# pcb.net
KiCad netlist of a schematic drawn in EAGLE
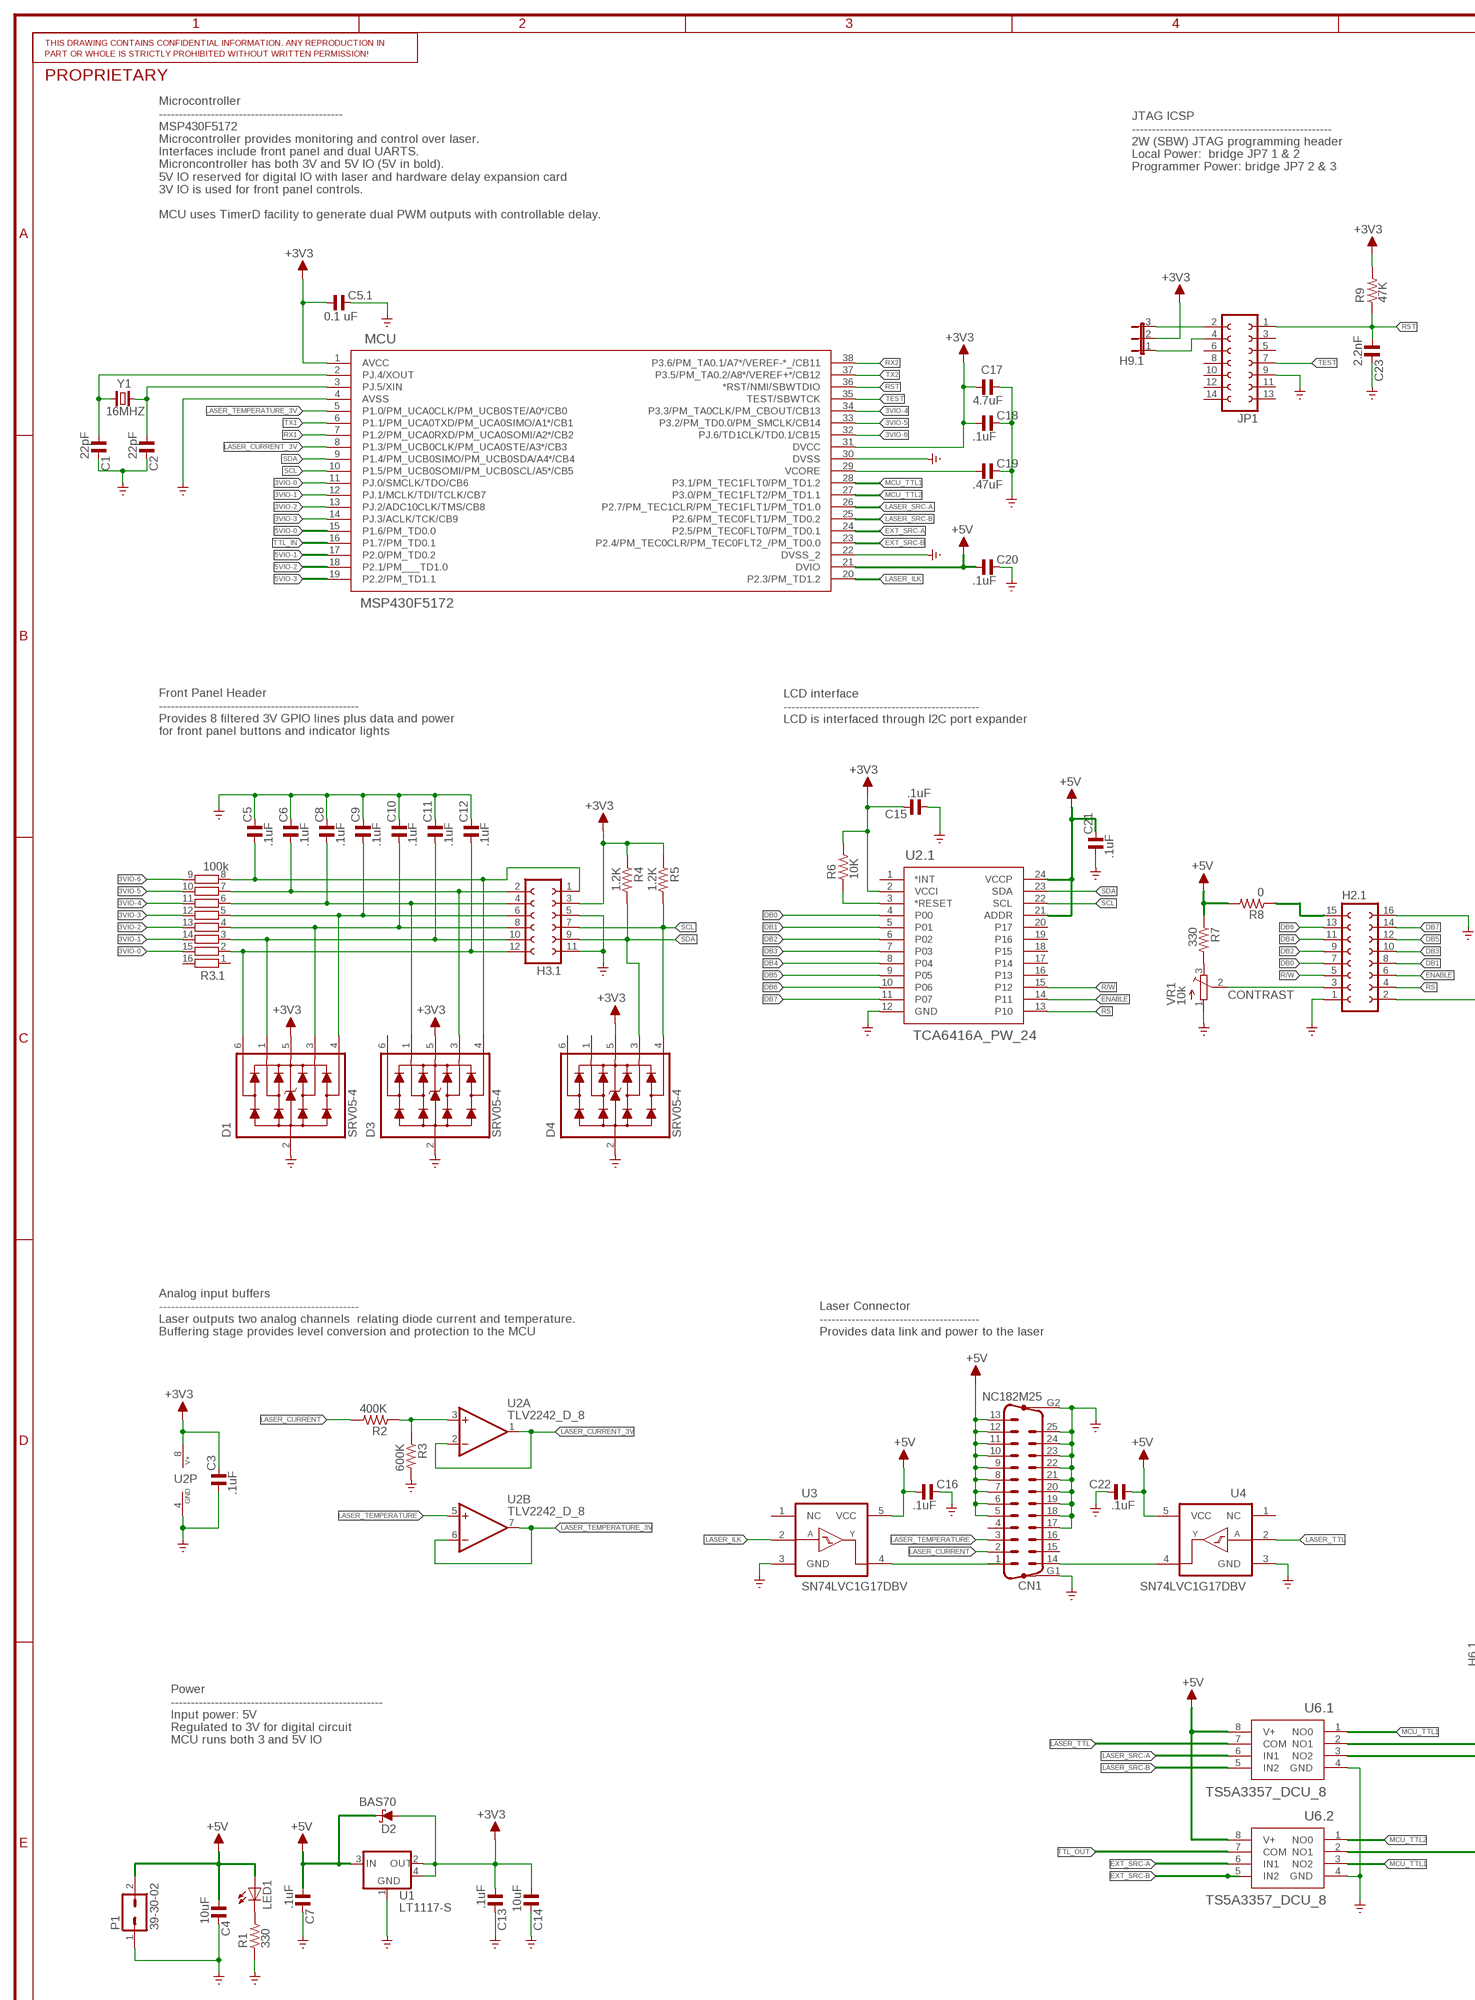
[diagram p0: schematic, sheet 1, part 1 of 3]
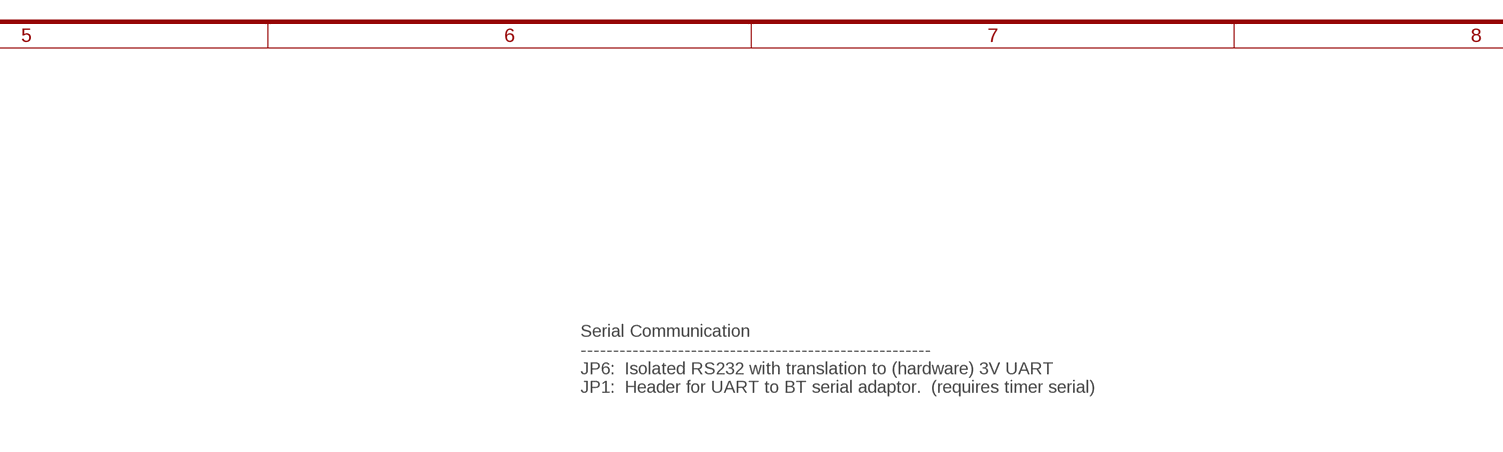
[diagram p1: schematic, sheet 1, part 2 of 3]
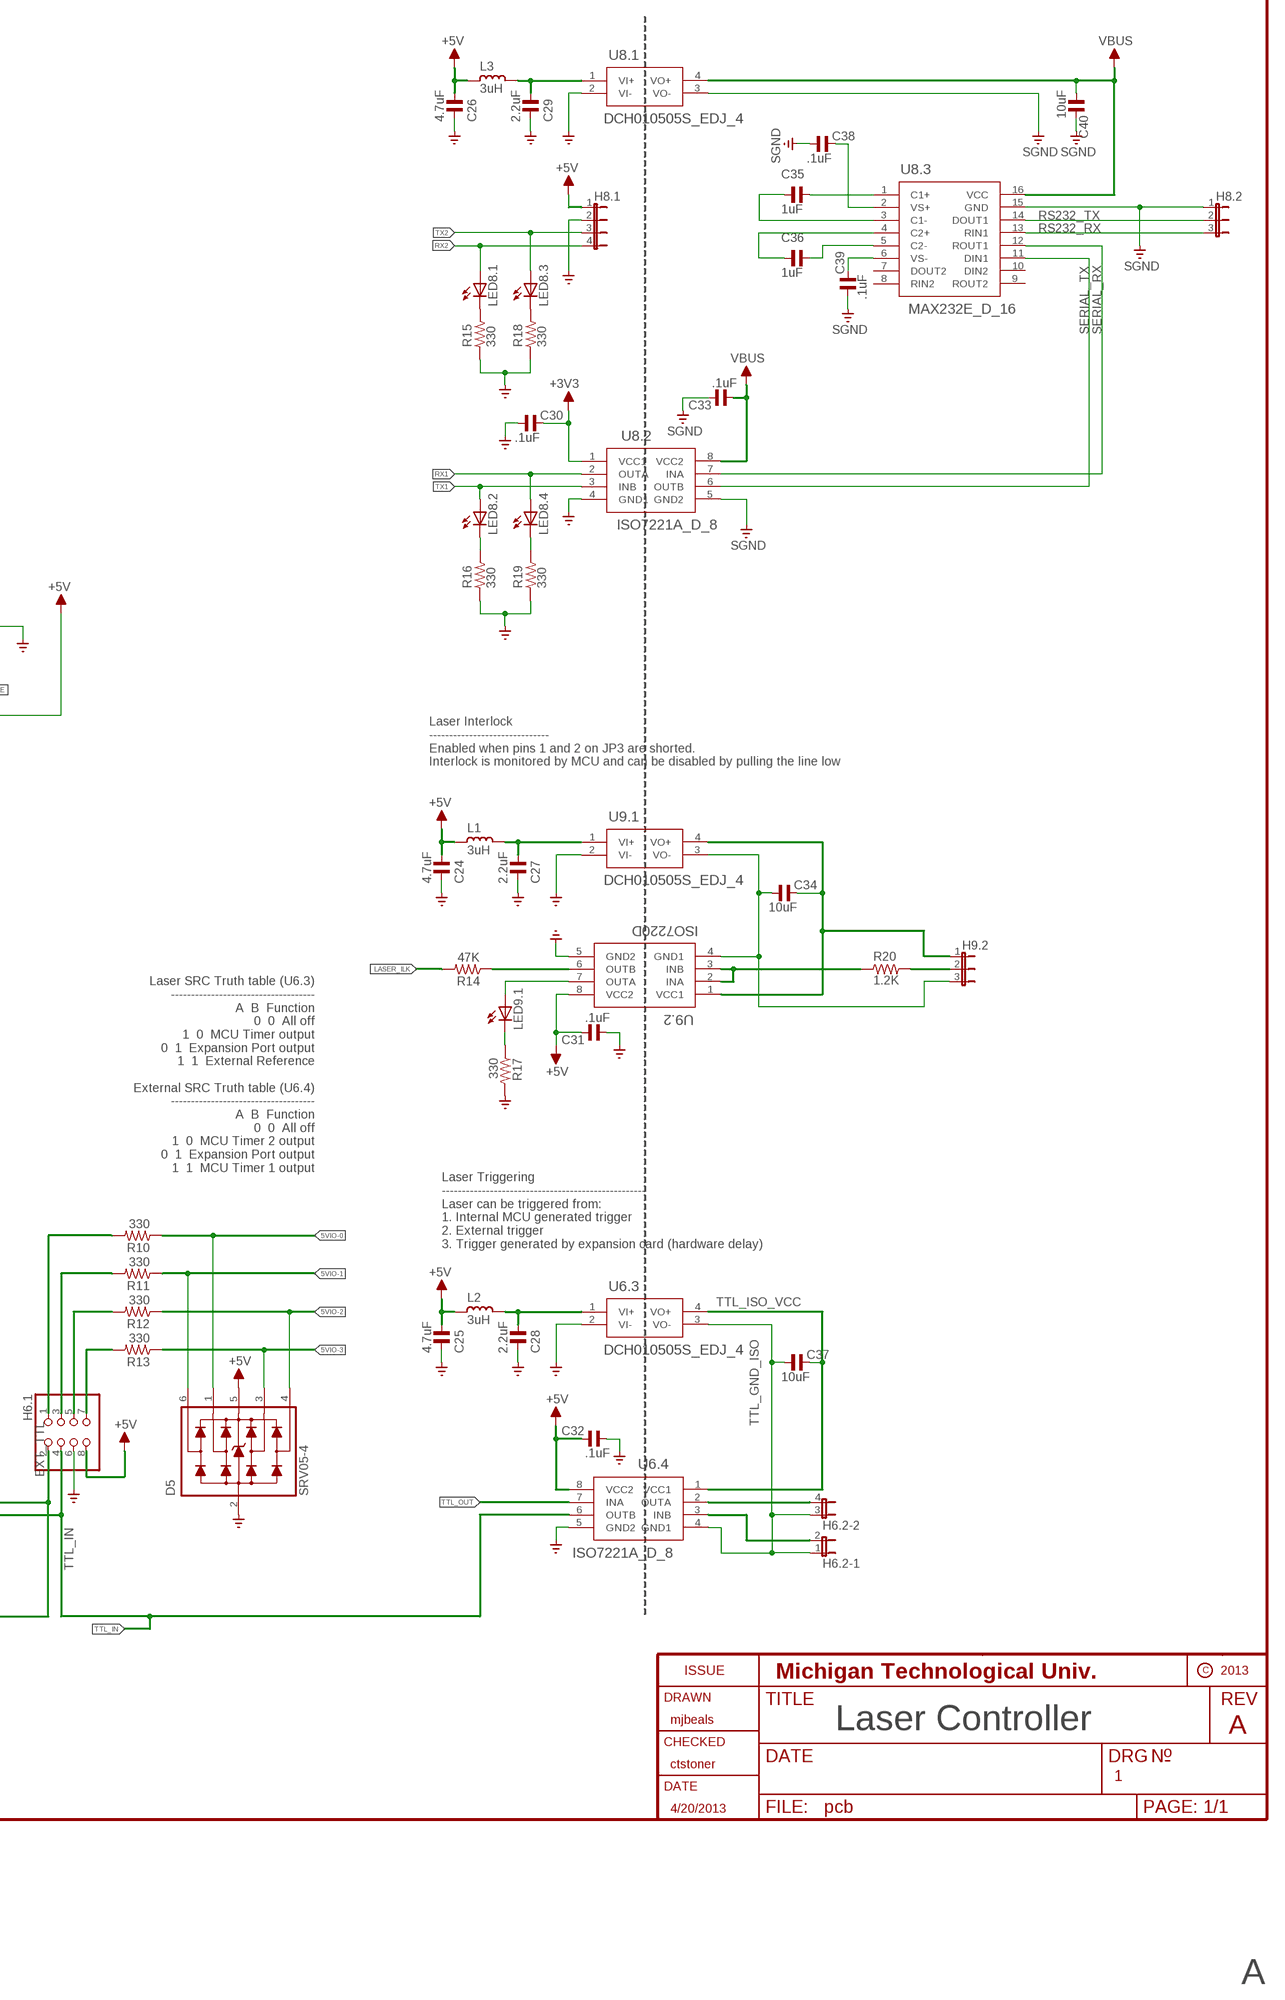
[diagram p2: schematic, sheet 1, part 3 of 3]

(export (version "E")
  (design (tool "Eeschema 10.0.6"))
  (components
    (comp (ref "C1")
      (value "22pF")
      (footprint "eagle-import:C0603")
      (libsource (lib "eagle-import") (part "C_0603"))
    )
    (comp (ref "C2")
      (value "22pF")
      (footprint "eagle-import:C0603")
      (libsource (lib "eagle-import") (part "C_0603"))
    )
    (comp (ref "C3")
      (value ".1uF")
      (footprint "eagle-import:C0603")
      (libsource (lib "eagle-import") (part "C_0603"))
    )
    (comp (ref "C4")
      (value "10uF")
      (footprint "eagle-import:C0603")
      (libsource (lib "eagle-import") (part "C_0603"))
    )
    (comp (ref "C5")
      (value ".1uF")
      (footprint "eagle-import:C0603")
      (libsource (lib "eagle-import") (part "C_0603"))
    )
    (comp (ref "C5.1")
      (value "0.1 uF")
      (footprint "eagle-import:C0603")
      (libsource (lib "eagle-import") (part "C_0603"))
    )
    (comp (ref "C6")
      (value ".1uF")
      (footprint "eagle-import:C0603")
      (libsource (lib "eagle-import") (part "C_0603"))
    )
    (comp (ref "C7")
      (value ".1uF")
      (footprint "eagle-import:C0603")
      (libsource (lib "eagle-import") (part "C_0603"))
    )
    (comp (ref "C8")
      (value ".1uF")
      (footprint "eagle-import:C0603")
      (libsource (lib "eagle-import") (part "C_0603"))
    )
    (comp (ref "C9")
      (value ".1uF")
      (footprint "eagle-import:C0603")
      (libsource (lib "eagle-import") (part "C_0603"))
    )
    (comp (ref "C10")
      (value ".1uF")
      (footprint "eagle-import:C0603")
      (libsource (lib "eagle-import") (part "C_0603"))
    )
    (comp (ref "C11")
      (value ".1uF")
      (footprint "eagle-import:C0603")
      (libsource (lib "eagle-import") (part "C_0603"))
    )
    (comp (ref "C12")
      (value ".1uF")
      (footprint "eagle-import:C0603")
      (libsource (lib "eagle-import") (part "C_0603"))
    )
    (comp (ref "C13")
      (value ".1uF")
      (footprint "eagle-import:C0603")
      (libsource (lib "eagle-import") (part "C_0603"))
    )
    (comp (ref "C14")
      (value "10uF")
      (footprint "eagle-import:C0603")
      (libsource (lib "eagle-import") (part "C_0603"))
    )
    (comp (ref "C15")
      (value ".1uF")
      (footprint "eagle-import:C0603")
      (libsource (lib "eagle-import") (part "C_0603"))
    )
    (comp (ref "C16")
      (value ".1uF")
      (footprint "eagle-import:C0603")
      (libsource (lib "eagle-import") (part "C_0603"))
    )
    (comp (ref "C17")
      (value "4.7uF")
      (footprint "eagle-import:C0603")
      (libsource (lib "eagle-import") (part "C_0603"))
    )
    (comp (ref "C18")
      (value ".1uF")
      (footprint "eagle-import:C0603")
      (libsource (lib "eagle-import") (part "C_0603"))
    )
    (comp (ref "C19")
      (value ".47uF")
      (footprint "eagle-import:C0603")
      (libsource (lib "eagle-import") (part "C_0603"))
    )
    (comp (ref "C20")
      (value ".1uF")
      (footprint "eagle-import:C0603")
      (libsource (lib "eagle-import") (part "C_0603"))
    )
    (comp (ref "C21")
      (value ".1uF")
      (footprint "eagle-import:C0603")
      (libsource (lib "eagle-import") (part "C_0603"))
    )
    (comp (ref "C22")
      (value ".1uF")
      (footprint "eagle-import:C0603")
      (libsource (lib "eagle-import") (part "C_0603"))
    )
    (comp (ref "C23")
      (value "2.2nF")
      (footprint "eagle-import:C0603")
      (libsource (lib "eagle-import") (part "C_0603"))
    )
    (comp (ref "C24")
      (value "4.7uF")
      (footprint "eagle-import:C0603")
      (libsource (lib "eagle-import") (part "C_0603"))
    )
    (comp (ref "C25")
      (value "4.7uF")
      (footprint "eagle-import:C0603")
      (libsource (lib "eagle-import") (part "C_0603"))
    )
    (comp (ref "C26")
      (value "4.7uF")
      (footprint "eagle-import:C0603")
      (libsource (lib "eagle-import") (part "C_0603"))
    )
    (comp (ref "C27")
      (value "2.2uF")
      (footprint "eagle-import:C0603")
      (libsource (lib "eagle-import") (part "C_0603"))
    )
    (comp (ref "C28")
      (value "2.2uF")
      (footprint "eagle-import:C0603")
      (libsource (lib "eagle-import") (part "C_0603"))
    )
    (comp (ref "C29")
      (value "2.2uF")
      (footprint "eagle-import:C0603")
      (libsource (lib "eagle-import") (part "C_0603"))
    )
    (comp (ref "C30")
      (value ".1uF")
      (footprint "eagle-import:C0603")
      (libsource (lib "eagle-import") (part "C_0603"))
    )
    (comp (ref "C31")
      (value ".1uF")
      (footprint "eagle-import:C0603")
      (libsource (lib "eagle-import") (part "C_0603"))
    )
    (comp (ref "C32")
      (value ".1uF")
      (footprint "eagle-import:C0603")
      (libsource (lib "eagle-import") (part "C_0603"))
    )
    (comp (ref "C33")
      (value ".1uF")
      (footprint "eagle-import:C0603")
      (libsource (lib "eagle-import") (part "C_0603"))
    )
    (comp (ref "C34")
      (value "10uF")
      (footprint "eagle-import:C0603")
      (libsource (lib "eagle-import") (part "C_0603"))
    )
    (comp (ref "C35")
      (value "1uF")
      (footprint "eagle-import:C0603")
      (libsource (lib "eagle-import") (part "C_0603"))
    )
    (comp (ref "C36")
      (value "1uF")
      (footprint "eagle-import:C0603")
      (libsource (lib "eagle-import") (part "C_0603"))
    )
    (comp (ref "C37")
      (value "10uF")
      (footprint "eagle-import:C0603")
      (libsource (lib "eagle-import") (part "C_0603"))
    )
    (comp (ref "C38")
      (value ".1uF")
      (footprint "eagle-import:C0603")
      (libsource (lib "eagle-import") (part "C_0603"))
    )
    (comp (ref "C39")
      (value ".1uF")
      (footprint "eagle-import:C0603")
      (libsource (lib "eagle-import") (part "C_0603"))
    )
    (comp (ref "C40")
      (value "10uF")
      (footprint "eagle-import:C0603")
      (libsource (lib "eagle-import") (part "C_0603"))
    )
    (comp (ref "CN1")
      (value "NC182M25")
      (footprint "eagle-import:NC182M25")
      (libsource (lib "eagle-import") (part "NC182M25"))
    )
    (comp (ref "D1")
      (value "SRV05-4")
      (footprint "eagle-import:SOT23-6L")
      (libsource (lib "eagle-import") (part "SRV05-4"))
    )
    (comp (ref "D2")
      (value "BAS70")
      (footprint "eagle-import:SOT23")
      (libsource (lib "eagle-import") (part "BAS70"))
    )
    (comp (ref "D3")
      (value "SRV05-4")
      (footprint "eagle-import:SOT23-6L")
      (libsource (lib "eagle-import") (part "SRV05-4"))
    )
    (comp (ref "D4")
      (value "SRV05-4")
      (footprint "eagle-import:SOT23-6L")
      (libsource (lib "eagle-import") (part "SRV05-4"))
    )
    (comp (ref "D5")
      (value "SRV05-4")
      (footprint "eagle-import:SOT23-6L")
      (libsource (lib "eagle-import") (part "SRV05-4"))
    )
    (comp (ref "H2.1")
      (value "FE08-2")
      (footprint "eagle-import:FE08-2")
      (libsource (lib "eagle-import") (part "FE08-2"))
    )
    (comp (ref "H3.1")
      (value "FE06-2")
      (footprint "eagle-import:FE06-2")
      (libsource (lib "eagle-import") (part "FE06-2"))
    )
    (comp (ref "H6.1")
      (value "PINHD-2X4")
      (footprint "eagle-import:2X04")
      (libsource (lib "eagle-import") (part "PINHD-2X4"))
    )
    (comp (ref "H6.2")
      (value "JP2QE")
      (footprint "eagle-import:JP2Q")
      (libsource (lib "eagle-import") (part "JP2QE"))
    )
    (comp (ref "H8.1")
      (value "JP4E")
      (footprint "eagle-import:JP4")
      (libsource (lib "eagle-import") (part "JP4E"))
    )
    (comp (ref "H8.2")
      (value "JP2E")
      (footprint "eagle-import:JP2")
      (libsource (lib "eagle-import") (part "JP2E"))
    )
    (comp (ref "H9.1")
      (value "JP2E")
      (footprint "eagle-import:JP2")
      (libsource (lib "eagle-import") (part "JP2E"))
    )
    (comp (ref "H9.2")
      (value "JP2E")
      (footprint "eagle-import:JP2")
      (libsource (lib "eagle-import") (part "JP2E"))
    )
    (comp (ref "JP1")
      (value "FE07-2")
      (footprint "eagle-import:FE07-2")
      (libsource (lib "eagle-import") (part "FE07-2"))
    )
    (comp (ref "L1")
      (value "3uH")
      (footprint "eagle-import:L0805")
      (libsource (lib "eagle-import") (part "L_0805"))
    )
    (comp (ref "L2")
      (value "3uH")
      (footprint "eagle-import:L0805")
      (libsource (lib "eagle-import") (part "L_0805"))
    )
    (comp (ref "L3")
      (value "3uH")
      (footprint "eagle-import:L0805")
      (libsource (lib "eagle-import") (part "L_0805"))
    )
    (comp (ref "LED1")
      (value "LEDSMT1206")
      (footprint "eagle-import:1206")
      (libsource (lib "eagle-import") (part "LEDSMT1206"))
    )
    (comp (ref "LED8.1")
      (value "LEDSMT1206")
      (footprint "eagle-import:1206")
      (libsource (lib "eagle-import") (part "LEDSMT1206"))
    )
    (comp (ref "LED8.2")
      (value "LEDSMT1206")
      (footprint "eagle-import:1206")
      (libsource (lib "eagle-import") (part "LEDSMT1206"))
    )
    (comp (ref "LED8.3")
      (value "LEDSMT1206")
      (footprint "eagle-import:1206")
      (libsource (lib "eagle-import") (part "LEDSMT1206"))
    )
    (comp (ref "LED8.4")
      (value "LEDSMT1206")
      (footprint "eagle-import:1206")
      (libsource (lib "eagle-import") (part "LEDSMT1206"))
    )
    (comp (ref "LED9.1")
      (value "LEDSMT1206")
      (footprint "eagle-import:1206")
      (libsource (lib "eagle-import") (part "LEDSMT1206"))
    )
    (comp (ref "MCU")
      (value "MSP430F5172")
      (footprint "eagle-import:DA38")
      (fields
        (field (name "MANUFACTURER") "Texas Instruments")
        (field (name "MANUFACTURER_PART_NUMBER") "msp430f5172_da_38")
      )
      (libsource (lib "eagle-import") (part "MSP430F5172_DA_38"))
    )
    (comp (ref "P1")
      (value "39-30-02")
      (footprint "eagle-import:39-30-_02_")
      (libsource (lib "eagle-import") (part "39-30-?02?"))
    )
    (comp (ref "R1")
      (value "330")
      (footprint "eagle-import:R0603")
      (libsource (lib "eagle-import") (part "R_0603"))
    )
    (comp (ref "R2")
      (value "400K")
      (footprint "eagle-import:R0603")
      (libsource (lib "eagle-import") (part "R_0603"))
    )
    (comp (ref "R3")
      (value "600K")
      (footprint "eagle-import:R0603")
      (libsource (lib "eagle-import") (part "R_0603"))
    )
    (comp (ref "R3.1")
      (value "100k")
      (footprint "eagle-import:2QSP16")
      (libsource (lib "eagle-import") (part "2QSP16-8"))
    )
    (comp (ref "R4")
      (value "1.2K")
      (footprint "eagle-import:R0603")
      (libsource (lib "eagle-import") (part "R_0603"))
    )
    (comp (ref "R5")
      (value "1.2K")
      (footprint "eagle-import:R0603")
      (libsource (lib "eagle-import") (part "R_0603"))
    )
    (comp (ref "R6")
      (value "10K")
      (footprint "eagle-import:R0603")
      (libsource (lib "eagle-import") (part "R_0603"))
    )
    (comp (ref "R7")
      (value "330")
      (footprint "eagle-import:R0603")
      (libsource (lib "eagle-import") (part "R_0603"))
    )
    (comp (ref "R8")
      (value "0")
      (footprint "eagle-import:R0603")
      (libsource (lib "eagle-import") (part "R_0603"))
    )
    (comp (ref "R9")
      (value "47K")
      (footprint "eagle-import:R0603")
      (libsource (lib "eagle-import") (part "R_0603"))
    )
    (comp (ref "R10")
      (value "330")
      (footprint "eagle-import:R0603")
      (libsource (lib "eagle-import") (part "R_0603"))
    )
    (comp (ref "R11")
      (value "330")
      (footprint "eagle-import:R0603")
      (libsource (lib "eagle-import") (part "R_0603"))
    )
    (comp (ref "R12")
      (value "330")
      (footprint "eagle-import:R0603")
      (libsource (lib "eagle-import") (part "R_0603"))
    )
    (comp (ref "R13")
      (value "330")
      (footprint "eagle-import:R0603")
      (libsource (lib "eagle-import") (part "R_0603"))
    )
    (comp (ref "R14")
      (value "47K")
      (footprint "eagle-import:R0603")
      (libsource (lib "eagle-import") (part "R_0603"))
    )
    (comp (ref "R15")
      (value "330")
      (footprint "eagle-import:R0603")
      (libsource (lib "eagle-import") (part "R_0603"))
    )
    (comp (ref "R16")
      (value "330")
      (footprint "eagle-import:R0603")
      (libsource (lib "eagle-import") (part "R_0603"))
    )
    (comp (ref "R17")
      (value "330")
      (footprint "eagle-import:R0603")
      (libsource (lib "eagle-import") (part "R_0603"))
    )
    (comp (ref "R18")
      (value "330")
      (footprint "eagle-import:R0603")
      (libsource (lib "eagle-import") (part "R_0603"))
    )
    (comp (ref "R19")
      (value "330")
      (footprint "eagle-import:R0603")
      (libsource (lib "eagle-import") (part "R_0603"))
    )
    (comp (ref "R20")
      (value "1.2K")
      (footprint "eagle-import:R0603")
      (libsource (lib "eagle-import") (part "R_0603"))
    )
    (comp (ref "U1")
      (value "LT1117-S")
      (footprint "eagle-import:SOT223")
      (libsource (lib "eagle-import") (part "LT1117-S"))
    )
    (comp (ref "U2")
      (value "TLV2242_D_8")
      (footprint "eagle-import:SO08")
      (libsource (lib "eagle-import") (part "LMV358D"))
    )
    (comp (ref "U2.1")
      (value "TCA6416A_PW_24")
      (footprint "eagle-import:PW24")
      (fields
        (field (name "GENERIC_PART_NUMBER") "TCA6416A")
        (field (name "MANUFACTURER") "Texas Instruments")
        (field (name "MANUFACTURER_PART_NUMBER") "tca6416a_pw_24")
      )
      (libsource (lib "eagle-import") (part "TCA6416A_PW_24"))
    )
    (comp (ref "U3")
      (value "SN74LVC1G17DBV")
      (footprint "eagle-import:SOT23-5")
      (libsource (lib "eagle-import") (part "SN74LVC1G17DBV"))
    )
    (comp (ref "U4")
      (value "SN74LVC1G17DBV")
      (footprint "eagle-import:SOT23-5")
      (libsource (lib "eagle-import") (part "SN74LVC1G17DBV"))
    )
    (comp (ref "U6.1")
      (value "TS5A3357_DCU_8")
      (footprint "eagle-import:DCU8")
      (fields
        (field (name "GENERIC_PART_NUMBER") "TS5A3357")
        (field (name "MANUFACTURER") "Texas Instruments")
        (field (name "MANUFACTURER_PART_NUMBER") "ts5a3357_dcu_8")
      )
      (libsource (lib "eagle-import") (part "TS5A3357_DCU_8"))
    )
    (comp (ref "U6.2")
      (value "TS5A3357_DCU_8")
      (footprint "eagle-import:DCU8")
      (fields
        (field (name "GENERIC_PART_NUMBER") "TS5A3357")
        (field (name "MANUFACTURER") "Texas Instruments")
        (field (name "MANUFACTURER_PART_NUMBER") "ts5a3357_dcu_8")
      )
      (libsource (lib "eagle-import") (part "TS5A3357_DCU_8"))
    )
    (comp (ref "U6.3")
      (value "DCH010505S_EDJ_4")
      (footprint "eagle-import:EDJ4")
      (fields
        (field (name "GENERIC_PART_NUMBER") "DCH010505S")
        (field (name "MANUFACTURER") "Texas Instruments")
        (field (name "MANUFACTURER_PART_NUMBER") "dch010505s_edj_4")
      )
      (libsource (lib "eagle-import") (part "DCH010505S_EDJ_4"))
    )
    (comp (ref "U6.4")
      (value "ISO7221A_D_8")
      (footprint "eagle-import:D8")
      (fields
        (field (name "GENERIC_PART_NUMBER") "ISO7221A")
        (field (name "MANUFACTURER") "Texas Instruments")
        (field (name "MANUFACTURER_PART_NUMBER") "iso7221a_d_8")
      )
      (libsource (lib "eagle-import") (part "ISO7221A_D_8"))
    )
    (comp (ref "U8.1")
      (value "DCH010505S_EDJ_4")
      (footprint "eagle-import:EDJ4")
      (fields
        (field (name "GENERIC_PART_NUMBER") "DCH010505S")
        (field (name "MANUFACTURER") "Texas Instruments")
        (field (name "MANUFACTURER_PART_NUMBER") "dch010505s_edj_4")
      )
      (libsource (lib "eagle-import") (part "DCH010505S_EDJ_4"))
    )
    (comp (ref "U8.2")
      (value "ISO7221A_D_8")
      (footprint "eagle-import:D8")
      (fields
        (field (name "GENERIC_PART_NUMBER") "ISO7221A")
        (field (name "MANUFACTURER") "Texas Instruments")
        (field (name "MANUFACTURER_PART_NUMBER") "iso7221a_d_8")
      )
      (libsource (lib "eagle-import") (part "ISO7221A_D_8"))
    )
    (comp (ref "U8.3")
      (value "MAX232E_D_16")
      (footprint "eagle-import:D16")
      (fields
        (field (name "GENERIC_PART_NUMBER") "MAX232E")
        (field (name "MANUFACTURER") "Texas Instruments")
        (field (name "MANUFACTURER_PART_NUMBER") "max232e_d_16")
      )
      (libsource (lib "eagle-import") (part "MAX232E_D_16"))
    )
    (comp (ref "U9.1")
      (value "DCH010505S_EDJ_4")
      (footprint "eagle-import:EDJ4")
      (fields
        (field (name "GENERIC_PART_NUMBER") "DCH010505S")
        (field (name "MANUFACTURER") "Texas Instruments")
        (field (name "MANUFACTURER_PART_NUMBER") "dch010505s_edj_4")
      )
      (libsource (lib "eagle-import") (part "DCH010505S_EDJ_4"))
    )
    (comp (ref "U9.2")
      (value "ISO7220D")
      (footprint "eagle-import:D8")
      (description "Low Power Dual Channel Isolators")
      (fields
        (field (name "GENERIC_PART_NUMBER") "ISO7420")
        (field (name "MANUFACTURER") "Texas Instruments")
        (field (name "MANUFACTURER_PART_NUMBER") "iso7420_d_8")
        (field (name "DATASHEETURL") "http://www.ti.com/lit/gpn/ISO7420")
        (field (name "GENERIC_PART_NUMBER_1") "ISO7420")
        (field (name "MANUFACTURER_PART_NUMBER_1") "iso7420_d_8")
      )
      (libsource (lib "eagle-import") (part "ISO7420_D_8"))
    )
    (comp (ref "VR1")
      (value "10k")
      (footprint "eagle-import:TC33X")
      (libsource (lib "eagle-import") (part "TRIMPOTTC33X"))
    )
    (comp (ref "Y1")
      (value "16MHZ")
      (footprint "eagle-import:HC49_S")
      (libsource (lib "eagle-import") (part "CRYTALHC49S"))
    )
  )
  (nets
    (net (code "1") (name "+3V3") (class "Default")
      (node (ref "C13") (pin "1") (pinfunction "1_1") (pintype "passive"))
      (node (ref "C14") (pin "1") (pinfunction "1_1") (pintype "passive"))
      (node (ref "C15") (pin "2") (pinfunction "2_2") (pintype "passive"))
      (node (ref "C17") (pin "1") (pinfunction "1_1") (pintype "passive"))
      (node (ref "C18") (pin "1") (pinfunction "1_1") (pintype "passive"))
      (node (ref "C3") (pin "2") (pinfunction "2_2") (pintype "passive"))
      (node (ref "C30") (pin "2") (pinfunction "2_2") (pintype "passive"))
      (node (ref "C5.1") (pin "1") (pinfunction "1_1") (pintype "passive"))
      (node (ref "D1") (pin "5") (pinfunction "5_5") (pintype "passive"))
      (node (ref "D2") (pin "1") (pinfunction "A_1") (pintype "passive"))
      (node (ref "D3") (pin "5") (pinfunction "5_5") (pintype "passive"))
      (node (ref "D4") (pin "5") (pinfunction "5_5") (pintype "passive"))
      (node (ref "H3.1") (pin "3") (pinfunction "3_3") (pintype "passive"))
      (node (ref "H9.1") (pin "2") (pinfunction "2_2") (pintype "passive"))
      (node (ref "MCU") (pin "1") (pinfunction "AVCC_1") (pintype "power_in"))
      (node (ref "MCU") (pin "31") (pinfunction "DVCC_31") (pintype "power_in"))
      (node (ref "R4") (pin "1") (pinfunction "1_1") (pintype "passive"))
      (node (ref "R5") (pin "1") (pinfunction "1_1") (pintype "passive"))
      (node (ref "R6") (pin "2") (pinfunction "2_2") (pintype "passive"))
      (node (ref "R9") (pin "2") (pinfunction "2_2") (pintype "passive"))
      (node (ref "U1") (pin "2") (pinfunction "OUT_2") (pintype "passive"))
      (node (ref "U1") (pin "4") (pinfunction "TAB_4") (pintype "passive"))
      (node (ref "U2") (pin "8") (pinfunction "V+_8") (pintype "power_in"))
      (node (ref "U2.1") (pin "2") (pinfunction "VCCI_2") (pintype "power_in"))
      (node (ref "U8.2") (pin "1") (pinfunction "VCC1_1") (pintype "power_in"))
    )
    (net (code "2") (name "+5V") (class "Default")
      (node (ref "C16") (pin "1") (pinfunction "1_1") (pintype "passive"))
      (node (ref "C20") (pin "1") (pinfunction "1_1") (pintype "passive"))
      (node (ref "C21") (pin "2") (pinfunction "2_2") (pintype "passive"))
      (node (ref "C22") (pin "1") (pinfunction "1_1") (pintype "passive"))
      (node (ref "C24") (pin "1") (pinfunction "1_1") (pintype "passive"))
      (node (ref "C25") (pin "1") (pinfunction "1_1") (pintype "passive"))
      (node (ref "C26") (pin "1") (pinfunction "1_1") (pintype "passive"))
      (node (ref "C31") (pin "2") (pinfunction "2_2") (pintype "passive"))
      (node (ref "C32") (pin "2") (pinfunction "2_2") (pintype "passive"))
      (node (ref "C4") (pin "1") (pinfunction "1_1") (pintype "passive"))
      (node (ref "C7") (pin "1") (pinfunction "1_1") (pintype "passive"))
      (node (ref "CN1") (pin "10") (pinfunction "10_10") (pintype "passive"))
      (node (ref "CN1") (pin "11") (pinfunction "11_11") (pintype "passive"))
      (node (ref "CN1") (pin "12") (pinfunction "12_12") (pintype "passive"))
      (node (ref "CN1") (pin "13") (pinfunction "13_13") (pintype "passive"))
      (node (ref "CN1") (pin "5") (pinfunction "5_5") (pintype "passive"))
      (node (ref "CN1") (pin "6") (pinfunction "6_6") (pintype "passive"))
      (node (ref "CN1") (pin "7") (pinfunction "7_7") (pintype "passive"))
      (node (ref "CN1") (pin "8") (pinfunction "8_8") (pintype "passive"))
      (node (ref "CN1") (pin "9") (pinfunction "9_9") (pintype "passive"))
      (node (ref "D2") (pin "3") (pinfunction "C_3") (pintype "passive"))
      (node (ref "D5") (pin "5") (pinfunction "5_5") (pintype "passive"))
      (node (ref "H2.1") (pin "2") (pinfunction "2_2") (pintype "passive"))
      (node (ref "H6.1") (pin "8") (pinfunction "8_8") (pintype "passive"))
      (node (ref "H8.1") (pin "1") (pinfunction "1_1") (pintype "passive"))
      (node (ref "L1") (pin "2") (pinfunction "2_2") (pintype "passive"))
      (node (ref "L2") (pin "2") (pinfunction "2_2") (pintype "passive"))
      (node (ref "L3") (pin "2") (pinfunction "2_2") (pintype "passive"))
      (node (ref "LED1") (pin "A") (pinfunction "A_A") (pintype "passive"))
      (node (ref "MCU") (pin "21") (pinfunction "DVIO_21") (pintype "power_in"))
      (node (ref "P1") (pin "2") (pinfunction "2_2") (pintype "passive"))
      (node (ref "R7") (pin "1") (pinfunction "1_1") (pintype "passive"))
      (node (ref "R8") (pin "2") (pinfunction "2_2") (pintype "passive"))
      (node (ref "U1") (pin "3") (pinfunction "IN_3") (pintype "input"))
      (node (ref "U2.1") (pin "21") (pinfunction "ADDR_21") (pintype "passive"))
      (node (ref "U2.1") (pin "24") (pinfunction "VCCP_24") (pintype "power_in"))
      (node (ref "U3") (pin "5") (pinfunction "VCC_5") (pintype "power_in"))
      (node (ref "U4") (pin "5") (pinfunction "VCC_5") (pintype "power_in"))
      (node (ref "U6.1") (pin "8") (pinfunction "V+_8") (pintype "power_in"))
      (node (ref "U6.2") (pin "8") (pinfunction "V+_8") (pintype "power_in"))
      (node (ref "U6.4") (pin "8") (pinfunction "VCC2_8") (pintype "power_in"))
      (node (ref "U9.2") (pin "8") (pinfunction "VCC2_8") (pintype "power_in"))
    )
    (net (code "3") (name "/CONTRAST") (class "Default")
      (node (ref "H2.1") (pin "3") (pinfunction "3_3") (pintype "passive"))
      (node (ref "VR1") (pin "2") (pinfunction "S_2") (pintype "passive"))
    )
    (net (code "4") (name "/EXT_TTL") (class "Default")
      (node (ref "H6.1") (pin "2") (pinfunction "2_2") (pintype "passive"))
      (node (ref "U6.1") (pin "2") (pinfunction "NO1_2") (pintype "passive"))
      (node (ref "U6.2") (pin "2") (pinfunction "NO1_2") (pintype "passive"))
    )
    (net (code "5") (name "/RS232_RX") (class "Default")
      (node (ref "H8.2") (pin "3") (pinfunction "3_3") (pintype "passive"))
      (node (ref "U8.3") (pin "13") (pinfunction "RIN1_13") (pintype "input"))
    )
    (net (code "6") (name "/RS232_TX") (class "Default")
      (node (ref "H8.2") (pin "2") (pinfunction "2_2") (pintype "passive"))
      (node (ref "U8.3") (pin "14") (pinfunction "DOUT1_14") (pintype "output"))
    )
    (net (code "7") (name "/SERIAL_RX") (class "Default")
      (node (ref "U8.2") (pin "7") (pinfunction "INA_7") (pintype "input"))
      (node (ref "U8.3") (pin "12") (pinfunction "ROUT1_12") (pintype "output"))
    )
    (net (code "8") (name "/SERIAL_TX") (class "Default")
      (node (ref "U8.2") (pin "6") (pinfunction "OUTB_6") (pintype "output"))
      (node (ref "U8.3") (pin "11") (pinfunction "DIN1_11") (pintype "input"))
    )
    (net (code "9") (name "/TTL_GND_ISO") (class "Default")
      (node (ref "C37") (pin "1") (pinfunction "1_1") (pintype "passive"))
      (node (ref "H6.2") (pin "1") (pinfunction "1_1") (pintype "passive"))
      (node (ref "H6.2") (pin "3") (pinfunction "1_3") (pintype "passive"))
      (node (ref "U6.3") (pin "3") (pinfunction "VO-_3") (pintype "output"))
      (node (ref "U6.4") (pin "4") (pinfunction "GND1_4") (pintype "power_in"))
    )
    (net (code "10") (name "/TTL_ISO_VCC") (class "Default")
      (node (ref "C37") (pin "2") (pinfunction "2_2") (pintype "passive"))
      (node (ref "U6.3") (pin "4") (pinfunction "VO+_4") (pintype "output"))
      (node (ref "U6.4") (pin "1") (pinfunction "VCC1_1") (pintype "power_in"))
    )
    (net (code "11") (name "3VIO-0") (class "Default")
      (node (ref "MCU") (pin "11") (pinfunction "PJ.0/SMCLK/TDO/CB6_11") (pintype "bidirectional"))
      (node (ref "R3.1") (pin "15") (pinfunction "15_15") (pintype "passive"))
    )
    (net (code "12") (name "3VIO-1") (class "Default")
      (node (ref "MCU") (pin "12") (pinfunction "PJ.1/MCLK/TDI/TCLK/CB7_12") (pintype "bidirectional"))
      (node (ref "R3.1") (pin "14") (pinfunction "14_14") (pintype "passive"))
    )
    (net (code "13") (name "3VIO-2") (class "Default")
      (node (ref "MCU") (pin "13") (pinfunction "PJ.2/ADC10CLK/TMS/CB8_13") (pintype "bidirectional"))
      (node (ref "R3.1") (pin "13") (pinfunction "13_13") (pintype "passive"))
    )
    (net (code "14") (name "3VIO-3") (class "Default")
      (node (ref "MCU") (pin "14") (pinfunction "PJ.3/ACLK/TCK/CB9_14") (pintype "bidirectional"))
      (node (ref "R3.1") (pin "12") (pinfunction "12_12") (pintype "passive"))
    )
    (net (code "15") (name "3VIO-4") (class "Default")
      (node (ref "MCU") (pin "34") (pinfunction "P3.3/PM_TA0CLK/PM_CBOUT/CB13_34") (pintype "bidirectional"))
      (node (ref "R3.1") (pin "11") (pinfunction "11_11") (pintype "passive"))
    )
    (net (code "16") (name "3VIO-5") (class "Default")
      (node (ref "MCU") (pin "33") (pinfunction "P3.2/PM_TD0.0/PM_SMCLK/CB14_33") (pintype "bidirectional"))
      (node (ref "R3.1") (pin "10") (pinfunction "10_10") (pintype "passive"))
    )
    (net (code "17") (name "3VIO-6") (class "Default")
      (node (ref "MCU") (pin "32") (pinfunction "PJ.6/TD1CLK/TD0.1/CB15_32") (pintype "bidirectional"))
      (node (ref "R3.1") (pin "9") (pinfunction "9_9") (pintype "passive"))
    )
    (net (code "18") (name "5VIO-0") (class "Default")
      (node (ref "D5") (pin "1") (pinfunction "1_1") (pintype "passive"))
      (node (ref "MCU") (pin "15") (pinfunction "P1.6/PM_TD0.0_15") (pintype "bidirectional"))
      (node (ref "R10") (pin "1") (pinfunction "1_1") (pintype "passive"))
    )
    (net (code "19") (name "5VIO-1") (class "Default")
      (node (ref "D5") (pin "6") (pinfunction "6_6") (pintype "passive"))
      (node (ref "MCU") (pin "17") (pinfunction "P2.0/PM_TD0.2_17") (pintype "bidirectional"))
      (node (ref "R11") (pin "1") (pinfunction "1_1") (pintype "passive"))
    )
    (net (code "20") (name "5VIO-2") (class "Default")
      (node (ref "D5") (pin "4") (pinfunction "4_4") (pintype "passive"))
      (node (ref "MCU") (pin "18") (pinfunction "P2.1/PM___TD1.0_18") (pintype "bidirectional"))
      (node (ref "R12") (pin "1") (pinfunction "1_1") (pintype "passive"))
    )
    (net (code "21") (name "5VIO-3") (class "Default")
      (node (ref "D5") (pin "3") (pinfunction "3_3") (pintype "passive"))
      (node (ref "MCU") (pin "19") (pinfunction "P2.2/PM_TD1.1_19") (pintype "bidirectional"))
      (node (ref "R13") (pin "1") (pinfunction "1_1") (pintype "passive"))
    )
    (net (code "22") (name "DB0") (class "Default")
      (node (ref "H2.1") (pin "7") (pinfunction "7_7") (pintype "passive"))
      (node (ref "U2.1") (pin "4") (pinfunction "P00_4") (pintype "output"))
    )
    (net (code "23") (name "DB1") (class "Default")
      (node (ref "H2.1") (pin "8") (pinfunction "8_8") (pintype "passive"))
      (node (ref "U2.1") (pin "5") (pinfunction "P01_5") (pintype "output"))
    )
    (net (code "24") (name "DB2") (class "Default")
      (node (ref "H2.1") (pin "9") (pinfunction "9_9") (pintype "passive"))
      (node (ref "U2.1") (pin "6") (pinfunction "P02_6") (pintype "output"))
    )
    (net (code "25") (name "DB3") (class "Default")
      (node (ref "H2.1") (pin "10") (pinfunction "10_10") (pintype "passive"))
      (node (ref "U2.1") (pin "7") (pinfunction "P03_7") (pintype "output"))
    )
    (net (code "26") (name "DB4") (class "Default")
      (node (ref "H2.1") (pin "11") (pinfunction "11_11") (pintype "passive"))
      (node (ref "U2.1") (pin "8") (pinfunction "P04_8") (pintype "output"))
    )
    (net (code "27") (name "DB5") (class "Default")
      (node (ref "H2.1") (pin "12") (pinfunction "12_12") (pintype "passive"))
      (node (ref "U2.1") (pin "9") (pinfunction "P05_9") (pintype "output"))
    )
    (net (code "28") (name "DB6") (class "Default")
      (node (ref "H2.1") (pin "13") (pinfunction "13_13") (pintype "passive"))
      (node (ref "U2.1") (pin "10") (pinfunction "P06_10") (pintype "output"))
    )
    (net (code "29") (name "DB7") (class "Default")
      (node (ref "H2.1") (pin "14") (pinfunction "14_14") (pintype "passive"))
      (node (ref "U2.1") (pin "11") (pinfunction "P07_11") (pintype "output"))
    )
    (net (code "30") (name "ENABLE") (class "Default")
      (node (ref "H2.1") (pin "6") (pinfunction "6_6") (pintype "passive"))
      (node (ref "U2.1") (pin "14") (pinfunction "P11_14") (pintype "output"))
    )
    (net (code "31") (name "EXT_SRC-A") (class "Default")
      (node (ref "MCU") (pin "24") (pinfunction "P2.5/PM_TEC0FLT0/PM_TD0.1_24") (pintype "bidirectional"))
      (node (ref "U6.2") (pin "6") (pinfunction "IN1_6") (pintype "input"))
    )
    (net (code "32") (name "EXT_SRC-B") (class "Default")
      (node (ref "MCU") (pin "23") (pinfunction "P2.4/PM_TEC0CLR/PM_TEC0FLT2_/PM_TD0.0_23") (pintype "bidirectional"))
      (node (ref "U6.2") (pin "5") (pinfunction "IN2_5") (pintype "input"))
    )
    (net (code "33") (name "GND") (class "Default")
      (node (ref "C1") (pin "2") (pinfunction "2_2") (pintype "passive"))
      (node (ref "C10") (pin "2") (pinfunction "2_2") (pintype "passive"))
      (node (ref "C11") (pin "2") (pinfunction "2_2") (pintype "passive"))
      (node (ref "C12") (pin "2") (pinfunction "2_2") (pintype "passive"))
      (node (ref "C13") (pin "2") (pinfunction "2_2") (pintype "passive"))
      (node (ref "C14") (pin "2") (pinfunction "2_2") (pintype "passive"))
      (node (ref "C15") (pin "1") (pinfunction "1_1") (pintype "passive"))
      (node (ref "C16") (pin "2") (pinfunction "2_2") (pintype "passive"))
      (node (ref "C17") (pin "2") (pinfunction "2_2") (pintype "passive"))
      (node (ref "C18") (pin "2") (pinfunction "2_2") (pintype "passive"))
      (node (ref "C19") (pin "2") (pinfunction "2_2") (pintype "passive"))
      (node (ref "C2") (pin "2") (pinfunction "2_2") (pintype "passive"))
      (node (ref "C20") (pin "2") (pinfunction "2_2") (pintype "passive"))
      (node (ref "C21") (pin "1") (pinfunction "1_1") (pintype "passive"))
      (node (ref "C22") (pin "2") (pinfunction "2_2") (pintype "passive"))
      (node (ref "C23") (pin "2") (pinfunction "2_2") (pintype "passive"))
      (node (ref "C24") (pin "2") (pinfunction "2_2") (pintype "passive"))
      (node (ref "C25") (pin "2") (pinfunction "2_2") (pintype "passive"))
      (node (ref "C26") (pin "2") (pinfunction "2_2") (pintype "passive"))
      (node (ref "C27") (pin "2") (pinfunction "2_2") (pintype "passive"))
      (node (ref "C28") (pin "2") (pinfunction "2_2") (pintype "passive"))
      (node (ref "C29") (pin "2") (pinfunction "2_2") (pintype "passive"))
      (node (ref "C3") (pin "1") (pinfunction "1_1") (pintype "passive"))
      (node (ref "C30") (pin "1") (pinfunction "1_1") (pintype "passive"))
      (node (ref "C31") (pin "1") (pinfunction "1_1") (pintype "passive"))
      (node (ref "C32") (pin "1") (pinfunction "1_1") (pintype "passive"))
      (node (ref "C4") (pin "2") (pinfunction "2_2") (pintype "passive"))
      (node (ref "C5") (pin "2") (pinfunction "2_2") (pintype "passive"))
      (node (ref "C5.1") (pin "2") (pinfunction "2_2") (pintype "passive"))
      (node (ref "C6") (pin "2") (pinfunction "2_2") (pintype "passive"))
      (node (ref "C7") (pin "2") (pinfunction "2_2") (pintype "passive"))
      (node (ref "C8") (pin "2") (pinfunction "2_2") (pintype "passive"))
      (node (ref "C9") (pin "2") (pinfunction "2_2") (pintype "passive"))
      (node (ref "CN1") (pin "17") (pinfunction "17_17") (pintype "passive"))
      (node (ref "CN1") (pin "18") (pinfunction "18_18") (pintype "passive"))
      (node (ref "CN1") (pin "19") (pinfunction "19_19") (pintype "passive"))
      (node (ref "CN1") (pin "20") (pinfunction "20_20") (pintype "passive"))
      (node (ref "CN1") (pin "21") (pinfunction "21_21") (pintype "passive"))
      (node (ref "CN1") (pin "22") (pinfunction "22_22") (pintype "passive"))
      (node (ref "CN1") (pin "23") (pinfunction "23_23") (pintype "passive"))
      (node (ref "CN1") (pin "24") (pinfunction "24_24") (pintype "passive"))
      (node (ref "CN1") (pin "25") (pinfunction "25_25") (pintype "passive"))
      (node (ref "CN1") (pin "G1") (pinfunction "G1_G1") (pintype "passive"))
      (node (ref "CN1") (pin "G2") (pinfunction "G2_G2") (pintype "passive"))
      (node (ref "D1") (pin "2") (pinfunction "2_2") (pintype "passive"))
      (node (ref "D3") (pin "2") (pinfunction "2_2") (pintype "passive"))
      (node (ref "D4") (pin "2") (pinfunction "2_2") (pintype "passive"))
      (node (ref "D5") (pin "2") (pinfunction "2_2") (pintype "passive"))
      (node (ref "H2.1") (pin "1") (pinfunction "1_1") (pintype "passive"))
      (node (ref "H2.1") (pin "16") (pinfunction "16_16") (pintype "passive"))
      (node (ref "H3.1") (pin "11") (pinfunction "11_11") (pintype "passive"))
      (node (ref "H3.1") (pin "5") (pinfunction "5_5") (pintype "passive"))
      (node (ref "H6.1") (pin "6") (pinfunction "6_6") (pintype "passive"))
      (node (ref "H8.1") (pin "2") (pinfunction "2_2") (pintype "passive"))
      (node (ref "JP1") (pin "9") (pinfunction "9_9") (pintype "passive"))
      (node (ref "MCU") (pin "22") (pinfunction "DVSS_2_22") (pintype "power_in"))
      (node (ref "MCU") (pin "30") (pinfunction "DVSS_30") (pintype "power_in"))
      (node (ref "MCU") (pin "4") (pinfunction "AVSS_4") (pintype "power_in"))
      (node (ref "P1") (pin "1") (pinfunction "1_1") (pintype "passive"))
      (node (ref "R1") (pin "1") (pinfunction "1_1") (pintype "passive"))
      (node (ref "R15") (pin "1") (pinfunction "1_1") (pintype "passive"))
      (node (ref "R16") (pin "1") (pinfunction "1_1") (pintype "passive"))
      (node (ref "R17") (pin "2") (pinfunction "2_2") (pintype "passive"))
      (node (ref "R18") (pin "1") (pinfunction "1_1") (pintype "passive"))
      (node (ref "R19") (pin "1") (pinfunction "1_1") (pintype "passive"))
      (node (ref "R3") (pin "2") (pinfunction "2_2") (pintype "passive"))
      (node (ref "U1") (pin "1") (pinfunction "GND_1") (pintype "input"))
      (node (ref "U2") (pin "4") (pinfunction "GND_4") (pintype "power_in"))
      (node (ref "U2.1") (pin "12") (pinfunction "GND_12") (pintype "power_in"))
      (node (ref "U3") (pin "3") (pinfunction "GND_3") (pintype "power_in"))
      (node (ref "U4") (pin "3") (pinfunction "GND_3") (pintype "power_in"))
      (node (ref "U6.1") (pin "4") (pinfunction "GND_4") (pintype "power_in"))
      (node (ref "U6.2") (pin "4") (pinfunction "GND_4") (pintype "power_in"))
      (node (ref "U6.3") (pin "2") (pinfunction "VI-_2") (pintype "input"))
      (node (ref "U6.4") (pin "5") (pinfunction "GND2_5") (pintype "power_in"))
      (node (ref "U8.1") (pin "2") (pinfunction "VI-_2") (pintype "input"))
      (node (ref "U8.2") (pin "4") (pinfunction "GND1_4") (pintype "power_in"))
      (node (ref "U9.1") (pin "2") (pinfunction "VI-_2") (pintype "input"))
      (node (ref "U9.2") (pin "5") (pinfunction "GND2_5") (pintype "power_in"))
      (node (ref "VR1") (pin "1") (pinfunction "A_1") (pintype "passive"))
    )
    (net (code "34") (name "LASER_CURRENT") (class "Default")
      (node (ref "CN1") (pin "2") (pinfunction "2_2") (pintype "passive"))
      (node (ref "R2") (pin "2") (pinfunction "2_2") (pintype "passive"))
    )
    (net (code "35") (name "LASER_CURRENT_3V") (class "Default")
      (node (ref "MCU") (pin "8") (pinfunction "P1.3/PM_UCB0CLK/PM_UCA0STE/A3*/CB3_8") (pintype "bidirectional"))
      (node (ref "U2") (pin "1") (pinfunction "OUT_1") (pintype "output"))
      (node (ref "U2") (pin "2") (pinfunction "-IN_2") (pintype "input"))
    )
    (net (code "36") (name "LASER_ILK") (class "Default")
      (node (ref "MCU") (pin "20") (pinfunction "P2.3/PM_TD1.2_20") (pintype "bidirectional"))
      (node (ref "R14") (pin "2") (pinfunction "2_2") (pintype "passive"))
      (node (ref "U3") (pin "2") (pinfunction "A_2") (pintype "input"))
    )
    (net (code "37") (name "LASER_SRC-A") (class "Default")
      (node (ref "MCU") (pin "26") (pinfunction "P2.7/PM_TEC1CLR/PM_TEC1FLT1/PM_TD1.0_26") (pintype "bidirectional"))
      (node (ref "U6.1") (pin "6") (pinfunction "IN1_6") (pintype "input"))
    )
    (net (code "38") (name "LASER_SRC-B") (class "Default")
      (node (ref "MCU") (pin "25") (pinfunction "P2.6/PM_TEC0FLT1/PM_TD0.2_25") (pintype "bidirectional"))
      (node (ref "U6.1") (pin "5") (pinfunction "IN2_5") (pintype "input"))
    )
    (net (code "39") (name "LASER_TEMPERATURE") (class "Default")
      (node (ref "CN1") (pin "3") (pinfunction "3_3") (pintype "passive"))
      (node (ref "U2") (pin "5") (pinfunction "+IN_5") (pintype "input"))
    )
    (net (code "40") (name "LASER_TEMPERATURE_3V") (class "Default")
      (node (ref "MCU") (pin "5") (pinfunction "P1.0/PM_UCA0CLK/PM_UCB0STE/A0*/CB0_5") (pintype "bidirectional"))
      (node (ref "U2") (pin "6") (pinfunction "-IN_6") (pintype "input"))
      (node (ref "U2") (pin "7") (pinfunction "OUT_7") (pintype "output"))
    )
    (net (code "41") (name "LASER_TTL") (class "Default")
      (node (ref "U4") (pin "2") (pinfunction "A_2") (pintype "input"))
      (node (ref "U6.1") (pin "7") (pinfunction "COM_7") (pintype "passive"))
    )
    (net (code "42") (name "MCU_TTL1") (class "Default")
      (node (ref "MCU") (pin "28") (pinfunction "P3.1/PM_TEC1FLT0/PM_TD1.2_28") (pintype "bidirectional"))
      (node (ref "U6.1") (pin "1") (pinfunction "NO0_1") (pintype "passive"))
      (node (ref "U6.2") (pin "3") (pinfunction "NO2_3") (pintype "passive"))
    )
    (net (code "43") (name "MCU_TTL2") (class "Default")
      (node (ref "MCU") (pin "27") (pinfunction "P3.0/PM_TEC1FLT2/PM_TD1.1_27") (pintype "bidirectional"))
      (node (ref "U6.2") (pin "1") (pinfunction "NO0_1") (pintype "passive"))
    )
    (net (code "44") (name "Net-(C5-Pad1)") (class "Default")
      (node (ref "C5") (pin "1") (pinfunction "1_1") (pintype "passive"))
      (node (ref "D3") (pin "4") (pinfunction "4_4") (pintype "passive"))
      (node (ref "H3.1") (pin "1") (pinfunction "1_1") (pintype "passive"))
      (node (ref "R3.1") (pin "8") (pinfunction "8_8") (pintype "passive"))
    )
    (net (code "45") (name "Net-(C6-Pad1)") (class "Default")
      (node (ref "C6") (pin "1") (pinfunction "1_1") (pintype "passive"))
      (node (ref "D3") (pin "3") (pinfunction "3_3") (pintype "passive"))
      (node (ref "H3.1") (pin "2") (pinfunction "2_2") (pintype "passive"))
      (node (ref "R3.1") (pin "7") (pinfunction "7_7") (pintype "passive"))
    )
    (net (code "46") (name "Net-(C8-Pad1)") (class "Default")
      (node (ref "C8") (pin "1") (pinfunction "1_1") (pintype "passive"))
      (node (ref "D3") (pin "1") (pinfunction "1_1") (pintype "passive"))
      (node (ref "H3.1") (pin "4") (pinfunction "4_4") (pintype "passive"))
      (node (ref "R3.1") (pin "6") (pinfunction "6_6") (pintype "passive"))
    )
    (net (code "47") (name "Net-(C9-Pad1)") (class "Default")
      (node (ref "C9") (pin "1") (pinfunction "1_1") (pintype "passive"))
      (node (ref "D1") (pin "4") (pinfunction "4_4") (pintype "passive"))
      (node (ref "H3.1") (pin "6") (pinfunction "6_6") (pintype "passive"))
      (node (ref "R3.1") (pin "5") (pinfunction "5_5") (pintype "passive"))
    )
    (net (code "48") (name "Net-(C10-Pad1)") (class "Default")
      (node (ref "C10") (pin "1") (pinfunction "1_1") (pintype "passive"))
      (node (ref "D1") (pin "3") (pinfunction "3_3") (pintype "passive"))
      (node (ref "H3.1") (pin "8") (pinfunction "8_8") (pintype "passive"))
      (node (ref "R3.1") (pin "4") (pinfunction "4_4") (pintype "passive"))
    )
    (net (code "49") (name "Net-(C11-Pad1)") (class "Default")
      (node (ref "C11") (pin "1") (pinfunction "1_1") (pintype "passive"))
      (node (ref "D1") (pin "1") (pinfunction "1_1") (pintype "passive"))
      (node (ref "H3.1") (pin "10") (pinfunction "10_10") (pintype "passive"))
      (node (ref "R3.1") (pin "3") (pinfunction "3_3") (pintype "passive"))
    )
    (net (code "50") (name "Net-(C12-Pad1)") (class "Default")
      (node (ref "C12") (pin "1") (pinfunction "1_1") (pintype "passive"))
      (node (ref "D1") (pin "6") (pinfunction "6_6") (pintype "passive"))
      (node (ref "H3.1") (pin "12") (pinfunction "12_12") (pintype "passive"))
      (node (ref "R3.1") (pin "2") (pinfunction "2_2") (pintype "passive"))
    )
    (net (code "51") (name "Net-(H2.1-Pad15)") (class "Default")
      (node (ref "H2.1") (pin "15") (pinfunction "15_15") (pintype "passive"))
      (node (ref "R8") (pin "1") (pinfunction "1_1") (pintype "passive"))
    )
    (net (code "52") (name "Net-(H6.1-Pad1)") (class "Default")
      (node (ref "H6.1") (pin "1") (pinfunction "1_1") (pintype "passive"))
      (node (ref "R10") (pin "2") (pinfunction "2_2") (pintype "passive"))
    )
    (net (code "53") (name "Net-(H6.1-Pad3)") (class "Default")
      (node (ref "H6.1") (pin "3") (pinfunction "3_3") (pintype "passive"))
      (node (ref "R11") (pin "2") (pinfunction "2_2") (pintype "passive"))
    )
    (net (code "54") (name "Net-(H6.1-Pad5)") (class "Default")
      (node (ref "H6.1") (pin "5") (pinfunction "5_5") (pintype "passive"))
      (node (ref "R12") (pin "2") (pinfunction "2_2") (pintype "passive"))
    )
    (net (code "55") (name "Net-(H6.1-Pad7)") (class "Default")
      (node (ref "H6.1") (pin "7") (pinfunction "7_7") (pintype "passive"))
      (node (ref "R13") (pin "2") (pinfunction "2_2") (pintype "passive"))
    )
    (net (code "56") (name "Net-(H6.2B-2)") (class "Default")
      (node (ref "H6.2") (pin "4") (pinfunction "2_4") (pintype "passive"))
      (node (ref "U6.4") (pin "2") (pinfunction "OUTA_2") (pintype "output"))
    )
    (net (code "57") (name "Net-(H9.1-Pad1)") (class "Default")
      (node (ref "H9.1") (pin "1") (pinfunction "1_1") (pintype "passive"))
      (node (ref "JP1") (pin "4") (pinfunction "4_4") (pintype "passive"))
    )
    (net (code "58") (name "Net-(H9.1-Pad3)") (class "Default")
      (node (ref "H9.1") (pin "3") (pinfunction "3_3") (pintype "passive"))
      (node (ref "JP1") (pin "2") (pinfunction "2_2") (pintype "passive"))
    )
    (net (code "59") (name "Net-(H9.2-Pad2)") (class "Default")
      (node (ref "H9.2") (pin "2") (pinfunction "2_2") (pintype "passive"))
      (node (ref "R20") (pin "2") (pinfunction "2_2") (pintype "passive"))
    )
    (net (code "60") (name "Net-(LED1-PadC)") (class "Default")
      (node (ref "LED1") (pin "C") (pinfunction "C_C") (pintype "passive"))
      (node (ref "R1") (pin "2") (pinfunction "2_2") (pintype "passive"))
    )
    (net (code "61") (name "Net-(LED8.1-PadC)") (class "Default")
      (node (ref "LED8.1") (pin "C") (pinfunction "C_C") (pintype "passive"))
      (node (ref "R15") (pin "2") (pinfunction "2_2") (pintype "passive"))
    )
    (net (code "62") (name "Net-(LED8.2-PadC)") (class "Default")
      (node (ref "LED8.2") (pin "C") (pinfunction "C_C") (pintype "passive"))
      (node (ref "R16") (pin "2") (pinfunction "2_2") (pintype "passive"))
    )
    (net (code "63") (name "Net-(LED8.3-PadC)") (class "Default")
      (node (ref "LED8.3") (pin "C") (pinfunction "C_C") (pintype "passive"))
      (node (ref "R18") (pin "2") (pinfunction "2_2") (pintype "passive"))
    )
    (net (code "64") (name "Net-(LED8.4-PadC)") (class "Default")
      (node (ref "LED8.4") (pin "C") (pinfunction "C_C") (pintype "passive"))
      (node (ref "R19") (pin "2") (pinfunction "2_2") (pintype "passive"))
    )
    (net (code "65") (name "Net-(LED9.1-PadC)") (class "Default")
      (node (ref "LED9.1") (pin "C") (pinfunction "C_C") (pintype "passive"))
      (node (ref "R17") (pin "1") (pinfunction "1_1") (pintype "passive"))
    )
    (net (code "66") (name "Net-(MCU-PJ.4{slash}XOUT)") (class "Default")
      (node (ref "C1") (pin "1") (pinfunction "1_1") (pintype "passive"))
      (node (ref "MCU") (pin "2") (pinfunction "PJ.4/XOUT_2") (pintype "bidirectional"))
      (node (ref "Y1") (pin "2") (pinfunction "2_2") (pintype "passive"))
    )
    (net (code "67") (name "Net-(MCU-PJ.5{slash}XIN)") (class "Default")
      (node (ref "C2") (pin "1") (pinfunction "1_1") (pintype "passive"))
      (node (ref "MCU") (pin "3") (pinfunction "PJ.5/XIN_3") (pintype "bidirectional"))
      (node (ref "Y1") (pin "1") (pinfunction "1_1") (pintype "passive"))
    )
    (net (code "68") (name "Net-(MCU-VCORE)") (class "Default")
      (node (ref "C19") (pin "1") (pinfunction "1_1") (pintype "passive"))
      (node (ref "MCU") (pin "29") (pinfunction "VCORE_29") (pintype "power_in"))
    )
    (net (code "69") (name "Net-(U2.1-*RESET)") (class "Default")
      (node (ref "R6") (pin "1") (pinfunction "1_1") (pintype "passive"))
      (node (ref "U2.1") (pin "3") (pinfunction "*RESET_3") (pintype "input"))
    )
    (net (code "70") (name "Net-(U2A-+IN)") (class "Default")
      (node (ref "R2") (pin "1") (pinfunction "1_1") (pintype "passive"))
      (node (ref "R3") (pin "1") (pinfunction "1_1") (pintype "passive"))
      (node (ref "U2") (pin "3") (pinfunction "+IN_3") (pintype "input"))
    )
    (net (code "71") (name "Net-(U3-Y)") (class "Default")
      (node (ref "CN1") (pin "1") (pinfunction "1_1") (pintype "passive"))
      (node (ref "U3") (pin "4") (pinfunction "Y_4") (pintype "output"))
    )
    (net (code "72") (name "Net-(U4-Y)") (class "Default")
      (node (ref "CN1") (pin "14") (pinfunction "14_14") (pintype "passive"))
      (node (ref "U4") (pin "4") (pinfunction "Y_4") (pintype "output"))
    )
    (net (code "73") (name "Net-(U6.3-VI+)") (class "Default")
      (node (ref "C28") (pin "1") (pinfunction "1_1") (pintype "passive"))
      (node (ref "L2") (pin "1") (pinfunction "1_1") (pintype "passive"))
      (node (ref "U6.3") (pin "1") (pinfunction "VI+_1") (pintype "input"))
    )
    (net (code "74") (name "Net-(U6.4-INB)") (class "Default")
      (node (ref "H6.2") (pin "2") (pinfunction "2_2") (pintype "passive"))
      (node (ref "U6.4") (pin "3") (pinfunction "INB_3") (pintype "input"))
    )
    (net (code "75") (name "Net-(U8.1-VI+)") (class "Default")
      (node (ref "C29") (pin "1") (pinfunction "1_1") (pintype "passive"))
      (node (ref "L3") (pin "1") (pinfunction "1_1") (pintype "passive"))
      (node (ref "U8.1") (pin "1") (pinfunction "VI+_1") (pintype "input"))
    )
    (net (code "76") (name "Net-(U8.3-C1+)") (class "Default")
      (node (ref "C35") (pin "2") (pinfunction "2_2") (pintype "passive"))
      (node (ref "U8.3") (pin "1") (pinfunction "C1+_1") (pintype "passive"))
    )
    (net (code "77") (name "Net-(U8.3-C1-)") (class "Default")
      (node (ref "C35") (pin "1") (pinfunction "1_1") (pintype "passive"))
      (node (ref "U8.3") (pin "3") (pinfunction "C1-_3") (pintype "passive"))
    )
    (net (code "78") (name "Net-(U8.3-C2+)") (class "Default")
      (node (ref "C36") (pin "1") (pinfunction "1_1") (pintype "passive"))
      (node (ref "U8.3") (pin "4") (pinfunction "C2+_4") (pintype "passive"))
    )
    (net (code "79") (name "Net-(U8.3-C2-)") (class "Default")
      (node (ref "C36") (pin "2") (pinfunction "2_2") (pintype "passive"))
      (node (ref "U8.3") (pin "5") (pinfunction "C2-_5") (pintype "passive"))
    )
    (net (code "80") (name "Net-(U8.3-VS+)") (class "Default")
      (node (ref "C38") (pin "2") (pinfunction "2_2") (pintype "passive"))
      (node (ref "U8.3") (pin "2") (pinfunction "VS+_2") (pintype "power_in"))
    )
    (net (code "81") (name "Net-(U8.3-VS-)") (class "Default")
      (node (ref "C39") (pin "2") (pinfunction "2_2") (pintype "passive"))
      (node (ref "U8.3") (pin "6") (pinfunction "VS-_6") (pintype "power_in"))
    )
    (net (code "82") (name "Net-(U9.1-VI+)") (class "Default")
      (node (ref "C27") (pin "1") (pinfunction "1_1") (pintype "passive"))
      (node (ref "L1") (pin "1") (pinfunction "1_1") (pintype "passive"))
      (node (ref "U9.1") (pin "1") (pinfunction "VI+_1") (pintype "input"))
    )
    (net (code "83") (name "Net-(U9.1-VO+)") (class "Default")
      (node (ref "C34") (pin "2") (pinfunction "2_2") (pintype "passive"))
      (node (ref "H9.2") (pin "1") (pinfunction "1_1") (pintype "passive"))
      (node (ref "U9.1") (pin "4") (pinfunction "VO+_4") (pintype "output"))
      (node (ref "U9.2") (pin "1") (pinfunction "VCC1_1") (pintype "power_in"))
    )
    (net (code "84") (name "Net-(U9.1-VO-)") (class "Default")
      (node (ref "C34") (pin "1") (pinfunction "1_1") (pintype "passive"))
      (node (ref "H9.2") (pin "3") (pinfunction "3_3") (pintype "passive"))
      (node (ref "U9.1") (pin "3") (pinfunction "VO-_3") (pintype "output"))
      (node (ref "U9.2") (pin "4") (pinfunction "GND1_4") (pintype "power_in"))
    )
    (net (code "85") (name "Net-(U9.2-INA)") (class "Default")
      (node (ref "R20") (pin "1") (pinfunction "1_1") (pintype "passive"))
      (node (ref "U9.2") (pin "2") (pinfunction "INA_2") (pintype "input"))
      (node (ref "U9.2") (pin "3") (pinfunction "INB_3") (pintype "input"))
    )
    (net (code "86") (name "Net-(U9.2-OUTA)") (class "Default")
      (node (ref "LED9.1") (pin "A") (pinfunction "A_A") (pintype "passive"))
      (node (ref "U9.2") (pin "7") (pinfunction "OUTA_7") (pintype "output"))
    )
    (net (code "87") (name "Net-(U9.2-OUTB)") (class "Default")
      (node (ref "R14") (pin "1") (pinfunction "1_1") (pintype "passive"))
      (node (ref "U9.2") (pin "6") (pinfunction "OUTB_6") (pintype "output"))
    )
    (net (code "88") (name "Net-(VR1-E)") (class "Default")
      (node (ref "R7") (pin "2") (pinfunction "2_2") (pintype "passive"))
      (node (ref "VR1") (pin "3") (pinfunction "E_3") (pintype "passive"))
    )
    (net (code "89") (name "RS") (class "Default")
      (node (ref "H2.1") (pin "4") (pinfunction "4_4") (pintype "passive"))
      (node (ref "U2.1") (pin "13") (pinfunction "P10_13") (pintype "output"))
    )
    (net (code "90") (name "RST") (class "Default")
      (node (ref "C23") (pin "1") (pinfunction "1_1") (pintype "passive"))
      (node (ref "JP1") (pin "1") (pinfunction "1_1") (pintype "passive"))
      (node (ref "MCU") (pin "36") (pinfunction "*RST/NMI/SBWTDIO_36") (pintype "bidirectional"))
      (node (ref "R9") (pin "1") (pinfunction "1_1") (pintype "passive"))
    )
    (net (code "91") (name "RX1") (class "Default")
      (node (ref "LED8.4") (pin "A") (pinfunction "A_A") (pintype "passive"))
      (node (ref "MCU") (pin "7") (pinfunction "P1.2/PM_UCA0RXD/PM_UCA0SOMI/A2*/CB2_7") (pintype "bidirectional"))
      (node (ref "U8.2") (pin "2") (pinfunction "OUTA_2") (pintype "output"))
    )
    (net (code "92") (name "RX2") (class "Default")
      (node (ref "H8.1") (pin "4") (pinfunction "4_4") (pintype "passive"))
      (node (ref "LED8.1") (pin "A") (pinfunction "A_A") (pintype "passive"))
      (node (ref "MCU") (pin "38") (pinfunction "P3.6/PM_TA0.1/A7*/VEREF-*_/CB11_38") (pintype "bidirectional"))
    )
    (net (code "93") (name "R{slash}W") (class "Default")
      (node (ref "H2.1") (pin "5") (pinfunction "5_5") (pintype "passive"))
      (node (ref "U2.1") (pin "15") (pinfunction "P12_15") (pintype "power_in"))
    )
    (net (code "94") (name "SCL") (class "Default")
      (node (ref "D4") (pin "4") (pinfunction "4_4") (pintype "passive"))
      (node (ref "H3.1") (pin "7") (pinfunction "7_7") (pintype "passive"))
      (node (ref "MCU") (pin "10") (pinfunction "P1.5/PM_UCB0SOMI/PM_UCB0SCL/A5*/CB5_10") (pintype "bidirectional"))
      (node (ref "R5") (pin "2") (pinfunction "2_2") (pintype "passive"))
      (node (ref "U2.1") (pin "22") (pinfunction "SCL_22") (pintype "passive"))
    )
    (net (code "95") (name "SDA") (class "Default")
      (node (ref "D4") (pin "3") (pinfunction "3_3") (pintype "passive"))
      (node (ref "H3.1") (pin "9") (pinfunction "9_9") (pintype "passive"))
      (node (ref "MCU") (pin "9") (pinfunction "P1.4/PM_UCB0SIMO/PM_UCB0SDA/A4*/CB4_9") (pintype "bidirectional"))
      (node (ref "R4") (pin "2") (pinfunction "2_2") (pintype "passive"))
      (node (ref "U2.1") (pin "23") (pinfunction "SDA_23") (pintype "passive"))
    )
    (net (code "96") (name "SGND") (class "Default")
      (node (ref "C33") (pin "2") (pinfunction "2_2") (pintype "passive"))
      (node (ref "C38") (pin "1") (pinfunction "1_1") (pintype "passive"))
      (node (ref "C39") (pin "1") (pinfunction "1_1") (pintype "passive"))
      (node (ref "C40") (pin "2") (pinfunction "2_2") (pintype "passive"))
      (node (ref "H8.2") (pin "1") (pinfunction "1_1") (pintype "passive"))
      (node (ref "U8.1") (pin "3") (pinfunction "VO-_3") (pintype "output"))
      (node (ref "U8.2") (pin "5") (pinfunction "GND2_5") (pintype "power_in"))
      (node (ref "U8.3") (pin "15") (pinfunction "GND_15") (pintype "power_in"))
    )
    (net (code "97") (name "TEST") (class "Default")
      (node (ref "JP1") (pin "7") (pinfunction "7_7") (pintype "passive"))
      (node (ref "MCU") (pin "35") (pinfunction "TEST/SBWTCK_35") (pintype "bidirectional"))
    )
    (net (code "98") (name "TTL_IN") (class "Default")
      (node (ref "H6.1") (pin "4") (pinfunction "4_4") (pintype "passive"))
      (node (ref "MCU") (pin "16") (pinfunction "P1.7/PM_TD0.1_16") (pintype "bidirectional"))
      (node (ref "U6.1") (pin "3") (pinfunction "NO2_3") (pintype "passive"))
      (node (ref "U6.4") (pin "6") (pinfunction "OUTB_6") (pintype "output"))
    )
    (net (code "99") (name "TTL_OUT") (class "Default")
      (node (ref "U6.2") (pin "7") (pinfunction "COM_7") (pintype "passive"))
      (node (ref "U6.4") (pin "7") (pinfunction "INA_7") (pintype "input"))
    )
    (net (code "100") (name "TX1") (class "Default")
      (node (ref "LED8.2") (pin "A") (pinfunction "A_A") (pintype "passive"))
      (node (ref "MCU") (pin "6") (pinfunction "P1.1/PM_UCA0TXD/PM_UCA0SIMO/A1*/CB1_6") (pintype "bidirectional"))
      (node (ref "U8.2") (pin "3") (pinfunction "INB_3") (pintype "input"))
    )
    (net (code "101") (name "TX2") (class "Default")
      (node (ref "H8.1") (pin "3") (pinfunction "3_3") (pintype "passive"))
      (node (ref "LED8.3") (pin "A") (pinfunction "A_A") (pintype "passive"))
      (node (ref "MCU") (pin "37") (pinfunction "P3.5/PM_TA0.2/A8*/VEREF+*/CB12_37") (pintype "bidirectional"))
    )
    (net (code "102") (name "VBUS") (class "Default")
      (node (ref "C33") (pin "1") (pinfunction "1_1") (pintype "passive"))
      (node (ref "C40") (pin "1") (pinfunction "1_1") (pintype "passive"))
      (node (ref "U8.1") (pin "4") (pinfunction "VO+_4") (pintype "output"))
      (node (ref "U8.2") (pin "8") (pinfunction "VCC2_8") (pintype "power_in"))
      (node (ref "U8.3") (pin "16") (pinfunction "VCC_16") (pintype "power_in"))
    )
    (net (code "103") (name "unconnected-(CN1-Pad4)") (class "Default")
      (node (ref "CN1") (pin "4") (pinfunction "4_4") (pintype "passive"))
    )
    (net (code "104") (name "unconnected-(CN1-Pad15)") (class "Default")
      (node (ref "CN1") (pin "15") (pinfunction "15_15") (pintype "passive"))
    )
    (net (code "105") (name "unconnected-(CN1-Pad16)") (class "Default")
      (node (ref "CN1") (pin "16") (pinfunction "16_16") (pintype "passive"))
    )
    (net (code "106") (name "unconnected-(D3-Pad6)") (class "Default")
      (node (ref "D3") (pin "6") (pinfunction "6_6") (pintype "passive"))
    )
    (net (code "107") (name "unconnected-(D4-Pad1)") (class "Default")
      (node (ref "D4") (pin "1") (pinfunction "1_1") (pintype "passive"))
    )
    (net (code "108") (name "unconnected-(D4-Pad6)") (class "Default")
      (node (ref "D4") (pin "6") (pinfunction "6_6") (pintype "passive"))
    )
    (net (code "109") (name "unconnected-(JP1-Pad3)") (class "Default")
      (node (ref "JP1") (pin "3") (pinfunction "3_3") (pintype "passive"))
    )
    (net (code "110") (name "unconnected-(JP1-Pad5)") (class "Default")
      (node (ref "JP1") (pin "5") (pinfunction "5_5") (pintype "passive"))
    )
    (net (code "111") (name "unconnected-(JP1-Pad6)") (class "Default")
      (node (ref "JP1") (pin "6") (pinfunction "6_6") (pintype "passive"))
    )
    (net (code "112") (name "unconnected-(JP1-Pad8)") (class "Default")
      (node (ref "JP1") (pin "8") (pinfunction "8_8") (pintype "passive"))
    )
    (net (code "113") (name "unconnected-(JP1-Pad10)") (class "Default")
      (node (ref "JP1") (pin "10") (pinfunction "10_10") (pintype "passive"))
    )
    (net (code "114") (name "unconnected-(JP1-Pad11)") (class "Default")
      (node (ref "JP1") (pin "11") (pinfunction "11_11") (pintype "passive"))
    )
    (net (code "115") (name "unconnected-(JP1-Pad12)") (class "Default")
      (node (ref "JP1") (pin "12") (pinfunction "12_12") (pintype "passive"))
    )
    (net (code "116") (name "unconnected-(JP1-Pad13)") (class "Default")
      (node (ref "JP1") (pin "13") (pinfunction "13_13") (pintype "passive"))
    )
    (net (code "117") (name "unconnected-(JP1-Pad14)") (class "Default")
      (node (ref "JP1") (pin "14") (pinfunction "14_14") (pintype "passive"))
    )
    (net (code "118") (name "unconnected-(R3.1-Pad1)") (class "Default")
      (node (ref "R3.1") (pin "1") (pinfunction "1_1") (pintype "passive"))
    )
    (net (code "119") (name "unconnected-(R3.1-Pad16)") (class "Default")
      (node (ref "R3.1") (pin "16") (pinfunction "16_16") (pintype "passive"))
    )
    (net (code "120") (name "unconnected-(U2.1-*INT-Pad1)") (class "Default")
      (node (ref "U2.1") (pin "1") (pinfunction "*INT_1") (pintype "output"))
    )
    (net (code "121") (name "unconnected-(U2.1-P13-Pad16)") (class "Default")
      (node (ref "U2.1") (pin "16") (pinfunction "P13_16") (pintype "output"))
    )
    (net (code "122") (name "unconnected-(U2.1-P14-Pad17)") (class "Default")
      (node (ref "U2.1") (pin "17") (pinfunction "P14_17") (pintype "output"))
    )
    (net (code "123") (name "unconnected-(U2.1-P15-Pad18)") (class "Default")
      (node (ref "U2.1") (pin "18") (pinfunction "P15_18") (pintype "output"))
    )
    (net (code "124") (name "unconnected-(U2.1-P16-Pad19)") (class "Default")
      (node (ref "U2.1") (pin "19") (pinfunction "P16_19") (pintype "output"))
    )
    (net (code "125") (name "unconnected-(U2.1-P17-Pad20)") (class "Default")
      (node (ref "U2.1") (pin "20") (pinfunction "P17_20") (pintype "output"))
    )
    (net (code "126") (name "unconnected-(U3-NC-Pad1)") (class "Default")
      (node (ref "U3") (pin "1") (pinfunction "NC_1") (pintype "no_connect"))
    )
    (net (code "127") (name "unconnected-(U4-NC-Pad1)") (class "Default")
      (node (ref "U4") (pin "1") (pinfunction "NC_1") (pintype "no_connect"))
    )
    (net (code "128") (name "unconnected-(U8.3-DIN2-Pad10)") (class "Default")
      (node (ref "U8.3") (pin "10") (pinfunction "DIN2_10") (pintype "input"))
    )
    (net (code "129") (name "unconnected-(U8.3-DOUT2-Pad7)") (class "Default")
      (node (ref "U8.3") (pin "7") (pinfunction "DOUT2_7") (pintype "output"))
    )
    (net (code "130") (name "unconnected-(U8.3-RIN2-Pad8)") (class "Default")
      (node (ref "U8.3") (pin "8") (pinfunction "RIN2_8") (pintype "input"))
    )
    (net (code "131") (name "unconnected-(U8.3-ROUT2-Pad9)") (class "Default")
      (node (ref "U8.3") (pin "9") (pinfunction "ROUT2_9") (pintype "output"))
    )
  )
)
